# 4fachsensor.net
KiCad netlist of a schematic drawn in EAGLE
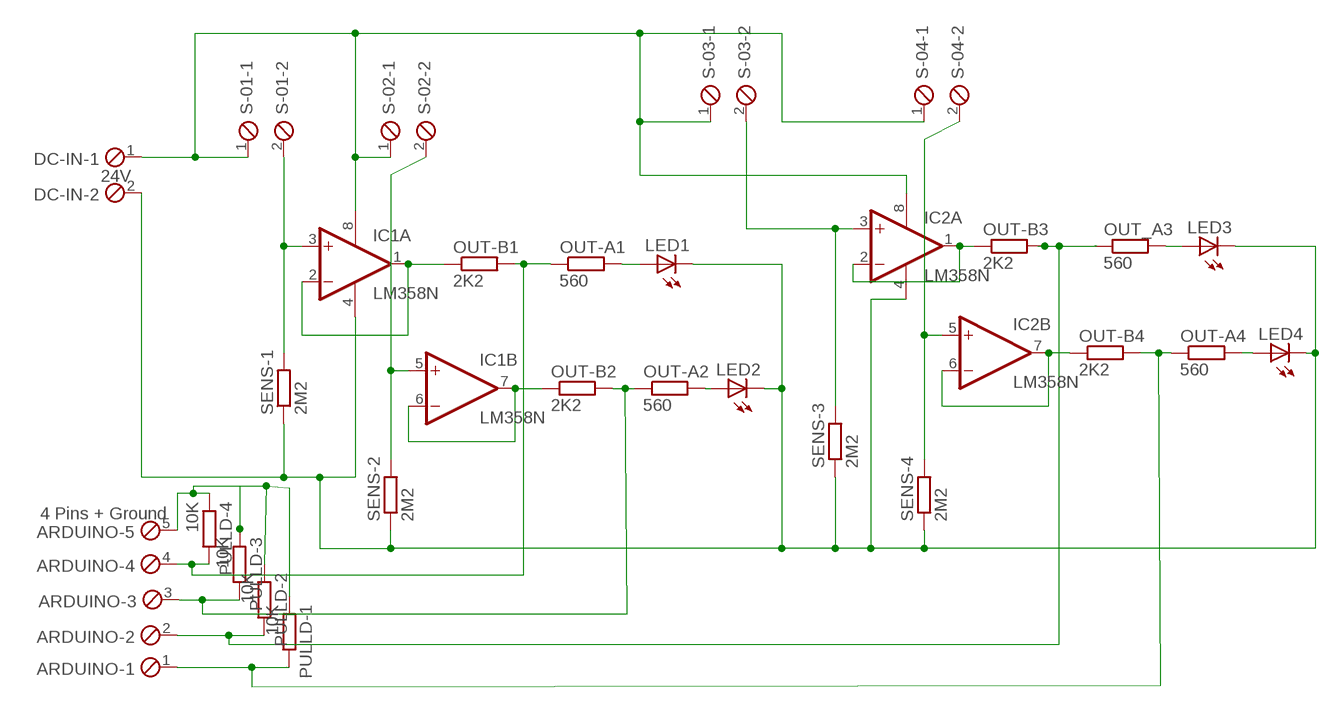
[diagram p0: schematic, sheet 1]

(export (version "E")
  (design (tool "Eeschema 10.0.6"))
  (components
    (comp (ref "ARDUINO")
      (value "4 Pins + Ground")
      (footprint "eagle-import:5POL254")
      (libsource (lib "eagle-import") (part "MPT5"))
    )
    (comp (ref "DC-IN")
      (value "24V")
      (footprint "eagle-import:2POL254")
      (libsource (lib "eagle-import") (part "MPT2"))
    )
    (comp (ref "IC1")
      (value "LM358N")
      (footprint "eagle-import:DIL08")
      (libsource (lib "eagle-import") (part "LM358N"))
    )
    (comp (ref "IC2")
      (value "LM358N")
      (footprint "eagle-import:DIL08")
      (libsource (lib "eagle-import") (part "LM358N"))
    )
    (comp (ref "LED1")
      (value "LED5MM")
      (footprint "eagle-import:LED5MM")
      (libsource (lib "eagle-import") (part "LED5MM"))
    )
    (comp (ref "LED2")
      (value "LED5MM")
      (footprint "eagle-import:LED5MM")
      (libsource (lib "eagle-import") (part "LED5MM"))
    )
    (comp (ref "LED3")
      (value "LED5MM")
      (footprint "eagle-import:LED5MM")
      (libsource (lib "eagle-import") (part "LED5MM"))
    )
    (comp (ref "LED4")
      (value "LED5MM")
      (footprint "eagle-import:LED5MM")
      (libsource (lib "eagle-import") (part "LED5MM"))
    )
    (comp (ref "OUT-A1")
      (value "560")
      (footprint "eagle-import:0207_7")
      (libsource (lib "eagle-import") (part "R-EU_0207/7"))
    )
    (comp (ref "OUT-A2")
      (value "560")
      (footprint "eagle-import:0207_7")
      (libsource (lib "eagle-import") (part "R-EU_0207/7"))
    )
    (comp (ref "OUT-A4")
      (value "560")
      (footprint "eagle-import:0207_7")
      (libsource (lib "eagle-import") (part "R-EU_0207/7"))
    )
    (comp (ref "OUT-B1")
      (value "2K2")
      (footprint "eagle-import:0207_7")
      (libsource (lib "eagle-import") (part "R-EU_0207/7"))
    )
    (comp (ref "OUT-B2")
      (value "2K2")
      (footprint "eagle-import:0207_7")
      (libsource (lib "eagle-import") (part "R-EU_0207/7"))
    )
    (comp (ref "OUT-B3")
      (value "2K2")
      (footprint "eagle-import:0207_7")
      (libsource (lib "eagle-import") (part "R-EU_0207/7"))
    )
    (comp (ref "OUT-B4")
      (value "2K2")
      (footprint "eagle-import:0207_7")
      (libsource (lib "eagle-import") (part "R-EU_0207/7"))
    )
    (comp (ref "OUT_A3")
      (value "560")
      (footprint "eagle-import:0207_7")
      (libsource (lib "eagle-import") (part "R-EU_0207/7"))
    )
    (comp (ref "PULLD-1")
      (value "10K")
      (footprint "eagle-import:0207_7")
      (libsource (lib "eagle-import") (part "R-EU_0207/7"))
    )
    (comp (ref "PULLD-2")
      (value "10K")
      (footprint "eagle-import:0207_7")
      (libsource (lib "eagle-import") (part "R-EU_0207/7"))
    )
    (comp (ref "PULLD-3")
      (value "10K")
      (footprint "eagle-import:0207_7")
      (libsource (lib "eagle-import") (part "R-EU_0207/7"))
    )
    (comp (ref "PULLD-4")
      (value "10K")
      (footprint "eagle-import:0207_7")
      (libsource (lib "eagle-import") (part "R-EU_0207/7"))
    )
    (comp (ref "S-01")
      (value "MPT2")
      (footprint "eagle-import:2POL254")
      (libsource (lib "eagle-import") (part "MPT2"))
    )
    (comp (ref "S-02")
      (value "MPT2")
      (footprint "eagle-import:2POL254")
      (libsource (lib "eagle-import") (part "MPT2"))
    )
    (comp (ref "S-03")
      (value "MPT2")
      (footprint "eagle-import:2POL254")
      (libsource (lib "eagle-import") (part "MPT2"))
    )
    (comp (ref "S-04")
      (value "MPT2")
      (footprint "eagle-import:2POL254")
      (libsource (lib "eagle-import") (part "MPT2"))
    )
    (comp (ref "SENS-1")
      (value "2M2")
      (footprint "eagle-import:0207_7")
      (libsource (lib "eagle-import") (part "R-EU_0207/7"))
    )
    (comp (ref "SENS-2")
      (value "2M2")
      (footprint "eagle-import:0207_7")
      (libsource (lib "eagle-import") (part "R-EU_0207/7"))
    )
    (comp (ref "SENS-3")
      (value "2M2")
      (footprint "eagle-import:0207_7")
      (libsource (lib "eagle-import") (part "R-EU_0207/7"))
    )
    (comp (ref "SENS-4")
      (value "2M2")
      (footprint "eagle-import:0207_7")
      (libsource (lib "eagle-import") (part "R-EU_0207/7"))
    )
  )
  (nets
    (net (code "1") (name "Net-(ARDUINO-Pad1)") (class "Default")
      (node (ref "ARDUINO") (pin "1") (pinfunction "1_1") (pintype "passive"))
      (node (ref "OUT-A4") (pin "1") (pinfunction "1_1") (pintype "passive"))
      (node (ref "OUT-B4") (pin "2") (pinfunction "2_2") (pintype "passive"))
      (node (ref "PULLD-1") (pin "2") (pinfunction "2_2") (pintype "passive"))
    )
    (net (code "2") (name "Net-(ARDUINOB-1)") (class "Default")
      (node (ref "ARDUINO") (pin "2") (pinfunction "1_2") (pintype "passive"))
      (node (ref "OUT-B3") (pin "2") (pinfunction "2_2") (pintype "passive"))
      (node (ref "OUT_A3") (pin "1") (pinfunction "1_1") (pintype "passive"))
      (node (ref "PULLD-2") (pin "2") (pinfunction "2_2") (pintype "passive"))
    )
    (net (code "3") (name "Net-(ARDUINOC-1)") (class "Default")
      (node (ref "ARDUINO") (pin "3") (pinfunction "1_3") (pintype "passive"))
      (node (ref "OUT-A2") (pin "1") (pinfunction "1_1") (pintype "passive"))
      (node (ref "OUT-B2") (pin "2") (pinfunction "2_2") (pintype "passive"))
      (node (ref "PULLD-3") (pin "2") (pinfunction "2_2") (pintype "passive"))
    )
    (net (code "4") (name "Net-(ARDUINOD-1)") (class "Default")
      (node (ref "ARDUINO") (pin "4") (pinfunction "1_4") (pintype "passive"))
      (node (ref "OUT-A1") (pin "1") (pinfunction "1_1") (pintype "passive"))
      (node (ref "OUT-B1") (pin "2") (pinfunction "2_2") (pintype "passive"))
      (node (ref "PULLD-4") (pin "2") (pinfunction "2_2") (pintype "passive"))
    )
    (net (code "5") (name "Net-(ARDUINOE-1)") (class "Default")
      (node (ref "ARDUINO") (pin "5") (pinfunction "1_5") (pintype "passive"))
      (node (ref "PULLD-1") (pin "1") (pinfunction "1_1") (pintype "passive"))
      (node (ref "PULLD-2") (pin "1") (pinfunction "1_1") (pintype "passive"))
      (node (ref "PULLD-3") (pin "1") (pinfunction "1_1") (pintype "passive"))
      (node (ref "PULLD-4") (pin "1") (pinfunction "1_1") (pintype "passive"))
    )
    (net (code "6") (name "Net-(DC-INB-1)") (class "Default")
      (node (ref "DC-IN") (pin "2") (pinfunction "1_2") (pintype "passive"))
      (node (ref "IC1") (pin "4") (pinfunction "V-_4") (pintype "power_in"))
      (node (ref "IC2") (pin "4") (pinfunction "V-_4") (pintype "power_in"))
      (node (ref "LED1") (pin "K") (pinfunction "C_K") (pintype "passive"))
      (node (ref "LED2") (pin "K") (pinfunction "C_K") (pintype "passive"))
      (node (ref "LED3") (pin "K") (pinfunction "C_K") (pintype "passive"))
      (node (ref "LED4") (pin "K") (pinfunction "C_K") (pintype "passive"))
      (node (ref "SENS-1") (pin "1") (pinfunction "1_1") (pintype "passive"))
      (node (ref "SENS-2") (pin "1") (pinfunction "1_1") (pintype "passive"))
      (node (ref "SENS-3") (pin "1") (pinfunction "1_1") (pintype "passive"))
      (node (ref "SENS-4") (pin "1") (pinfunction "1_1") (pintype "passive"))
    )
    (net (code "7") (name "Net-(IC1A-+IN)") (class "Default")
      (node (ref "IC1") (pin "3") (pinfunction "+IN_3") (pintype "input"))
      (node (ref "S-01") (pin "2") (pinfunction "1_2") (pintype "passive"))
      (node (ref "SENS-1") (pin "2") (pinfunction "2_2") (pintype "passive"))
    )
    (net (code "8") (name "Net-(IC1A--IN)") (class "Default")
      (node (ref "IC1") (pin "1") (pinfunction "OUT_1") (pintype "output"))
      (node (ref "IC1") (pin "2") (pinfunction "-IN_2") (pintype "input"))
      (node (ref "OUT-B1") (pin "1") (pinfunction "1_1") (pintype "passive"))
    )
    (net (code "9") (name "Net-(IC1B-+IN)") (class "Default")
      (node (ref "IC1") (pin "5") (pinfunction "+IN_5") (pintype "input"))
      (node (ref "S-02") (pin "2") (pinfunction "1_2") (pintype "passive"))
      (node (ref "SENS-2") (pin "2") (pinfunction "2_2") (pintype "passive"))
    )
    (net (code "10") (name "Net-(IC1B--IN)") (class "Default")
      (node (ref "IC1") (pin "6") (pinfunction "-IN_6") (pintype "input"))
      (node (ref "IC1") (pin "7") (pinfunction "OUT_7") (pintype "output"))
      (node (ref "OUT-B2") (pin "1") (pinfunction "1_1") (pintype "passive"))
    )
    (net (code "11") (name "Net-(IC1C-V+)") (class "Default")
      (node (ref "DC-IN") (pin "1") (pinfunction "1_1") (pintype "passive"))
      (node (ref "IC1") (pin "8") (pinfunction "V+_8") (pintype "power_in"))
      (node (ref "IC2") (pin "8") (pinfunction "V+_8") (pintype "power_in"))
      (node (ref "S-01") (pin "1") (pinfunction "1_1") (pintype "passive"))
      (node (ref "S-02") (pin "1") (pinfunction "1_1") (pintype "passive"))
      (node (ref "S-03") (pin "1") (pinfunction "1_1") (pintype "passive"))
      (node (ref "S-04") (pin "1") (pinfunction "1_1") (pintype "passive"))
    )
    (net (code "12") (name "Net-(IC2A-+IN)") (class "Default")
      (node (ref "IC2") (pin "3") (pinfunction "+IN_3") (pintype "input"))
      (node (ref "S-03") (pin "2") (pinfunction "1_2") (pintype "passive"))
      (node (ref "SENS-3") (pin "2") (pinfunction "2_2") (pintype "passive"))
    )
    (net (code "13") (name "Net-(IC2A--IN)") (class "Default")
      (node (ref "IC2") (pin "1") (pinfunction "OUT_1") (pintype "output"))
      (node (ref "IC2") (pin "2") (pinfunction "-IN_2") (pintype "input"))
      (node (ref "OUT-B3") (pin "1") (pinfunction "1_1") (pintype "passive"))
    )
    (net (code "14") (name "Net-(IC2B-+IN)") (class "Default")
      (node (ref "IC2") (pin "5") (pinfunction "+IN_5") (pintype "input"))
      (node (ref "S-04") (pin "2") (pinfunction "1_2") (pintype "passive"))
      (node (ref "SENS-4") (pin "2") (pinfunction "2_2") (pintype "passive"))
    )
    (net (code "15") (name "Net-(IC2B--IN)") (class "Default")
      (node (ref "IC2") (pin "6") (pinfunction "-IN_6") (pintype "input"))
      (node (ref "IC2") (pin "7") (pinfunction "OUT_7") (pintype "output"))
      (node (ref "OUT-B4") (pin "1") (pinfunction "1_1") (pintype "passive"))
    )
    (net (code "16") (name "Net-(LED1-PadA)") (class "Default")
      (node (ref "LED1") (pin "A") (pinfunction "A_A") (pintype "passive"))
      (node (ref "OUT-A1") (pin "2") (pinfunction "2_2") (pintype "passive"))
    )
    (net (code "17") (name "Net-(LED2-PadA)") (class "Default")
      (node (ref "LED2") (pin "A") (pinfunction "A_A") (pintype "passive"))
      (node (ref "OUT-A2") (pin "2") (pinfunction "2_2") (pintype "passive"))
    )
    (net (code "18") (name "Net-(LED3-PadA)") (class "Default")
      (node (ref "LED3") (pin "A") (pinfunction "A_A") (pintype "passive"))
      (node (ref "OUT_A3") (pin "2") (pinfunction "2_2") (pintype "passive"))
    )
    (net (code "19") (name "Net-(LED4-PadA)") (class "Default")
      (node (ref "LED4") (pin "A") (pinfunction "A_A") (pintype "passive"))
      (node (ref "OUT-A4") (pin "2") (pinfunction "2_2") (pintype "passive"))
    )
  )
)
